# Reset.net
KiCad netlist of a schematic drawn in Altium Designer
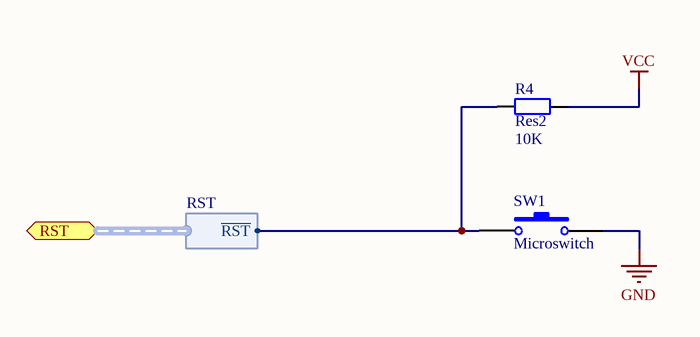
[diagram p0: Reset.SchDoc]

(export (version "E")
  (design (tool "Eeschema 10.0.6"))
  (components
    (comp (ref "R4")
      (value "Res2")
      (footprint "AXIAL-0.4")
      (description "Resistor")
      (fields (field (name "ALTIUM_VALUE") "10K") (field (name "PUBLISHER") "Altium Limited"))
      (libsource (lib "Miscellaneous Devices") (part "Res2"))
    )
    (comp (ref "SW1")
      (value "Microswitch")
      (footprint "DIP Microswitch 6x6mm")
      (libsource (lib "Components") (part "Microswitch"))
    )
  )
  (nets
    (net (code "3") (name "GND") (class "Default")
      (node (ref "SW1") (pin "2") (pinfunction "2_2") (pintype "passive"))
    )
    (net (code "4") (name "Net-(R4-Pad1)") (class "Default")
      (node (ref "R4") (pin "1") (pinfunction "1_1") (pintype "passive"))
      (node (ref "SW1") (pin "1") (pinfunction "1_1") (pintype "passive"))
    )
    (net (code "5") (name "VCC") (class "Default")
      (node (ref "R4") (pin "2") (pinfunction "2_2") (pintype "passive"))
    )
  )
)
